# ADC.net
KiCad netlist of a schematic drawn in Altium Designer
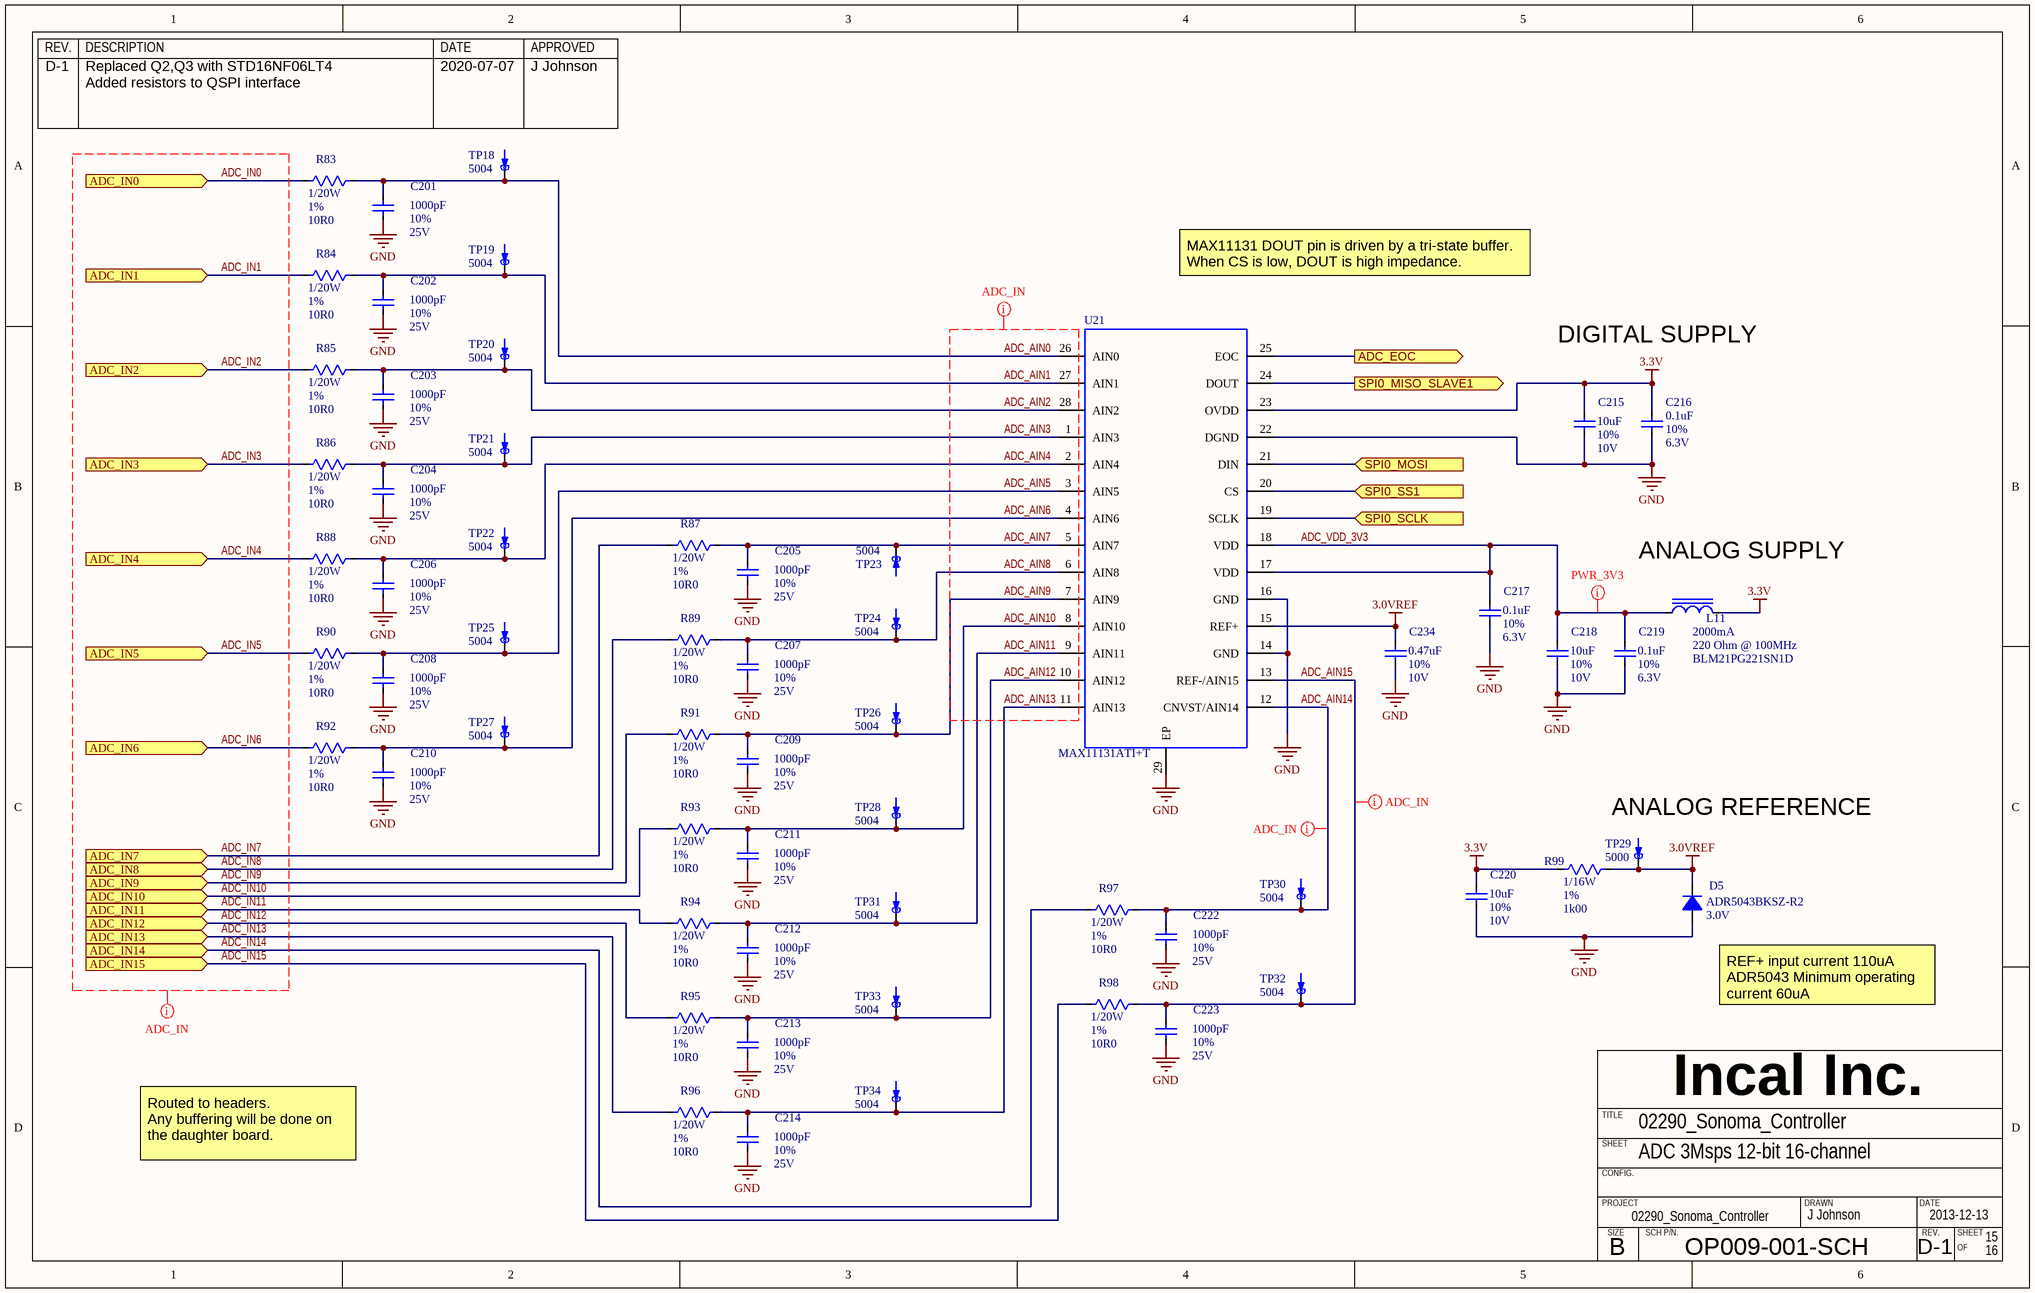
[diagram p0: ADC.SchDoc]

(export (version "E")
  (design (tool "Eeschema 10.0.6"))
  (components
    (comp (ref "C201")
      (value "1000pF")
      (footprint "CAPC0603X33N")
      (description "Capacitor ceramic, X5R, 1000pF, 25V, 10%, -55 to +85 C, EIA0201")
      (fields
        (field (name "TOLERANCE") "10%")
        (field (name "VOLTAGE") "25V")
        (field (name "Comment") "CAPACITOR_NP_TYPE1")
      )
      (libsource (lib "parts") (part "CAPACITOR_NP_TYPE1"))
    )
    (comp (ref "C202")
      (value "1000pF")
      (footprint "CAPC0603X33N")
      (description "Capacitor ceramic, X5R, 1000pF, 25V, 10%, -55 to +85 C, EIA0201")
      (fields
        (field (name "TOLERANCE") "10%")
        (field (name "VOLTAGE") "25V")
        (field (name "Comment") "CAPACITOR_NP_TYPE1")
      )
      (libsource (lib "parts") (part "CAPACITOR_NP_TYPE1"))
    )
    (comp (ref "C203")
      (value "1000pF")
      (footprint "CAPC0603X33N")
      (description "Capacitor ceramic, X5R, 1000pF, 25V, 10%, -55 to +85 C, EIA0201")
      (fields
        (field (name "TOLERANCE") "10%")
        (field (name "VOLTAGE") "25V")
        (field (name "Comment") "CAPACITOR_NP_TYPE1")
      )
      (libsource (lib "parts") (part "CAPACITOR_NP_TYPE1"))
    )
    (comp (ref "C204")
      (value "1000pF")
      (footprint "CAPC0603X33N")
      (description "Capacitor ceramic, X5R, 1000pF, 25V, 10%, -55 to +85 C, EIA0201")
      (fields
        (field (name "TOLERANCE") "10%")
        (field (name "VOLTAGE") "25V")
        (field (name "Comment") "CAPACITOR_NP_TYPE1")
      )
      (libsource (lib "parts") (part "CAPACITOR_NP_TYPE1"))
    )
    (comp (ref "C205")
      (value "1000pF")
      (footprint "CAPC0603X33N")
      (description "Capacitor ceramic, X5R, 1000pF, 25V, 10%, -55 to +85 C, EIA0201")
      (fields
        (field (name "TOLERANCE") "10%")
        (field (name "VOLTAGE") "25V")
        (field (name "Comment") "CAPACITOR_NP_TYPE1")
      )
      (libsource (lib "parts") (part "CAPACITOR_NP_TYPE1"))
    )
    (comp (ref "C206")
      (value "1000pF")
      (footprint "CAPC0603X33N")
      (description "Capacitor ceramic, X5R, 1000pF, 25V, 10%, -55 to +85 C, EIA0201")
      (fields
        (field (name "TOLERANCE") "10%")
        (field (name "VOLTAGE") "25V")
        (field (name "Comment") "CAPACITOR_NP_TYPE1")
      )
      (libsource (lib "parts") (part "CAPACITOR_NP_TYPE1"))
    )
    (comp (ref "C207")
      (value "1000pF")
      (footprint "CAPC0603X33N")
      (description "Capacitor ceramic, X5R, 1000pF, 25V, 10%, -55 to +85 C, EIA0201")
      (fields
        (field (name "TOLERANCE") "10%")
        (field (name "VOLTAGE") "25V")
        (field (name "Comment") "CAPACITOR_NP_TYPE1")
      )
      (libsource (lib "parts") (part "CAPACITOR_NP_TYPE1"))
    )
    (comp (ref "C208")
      (value "1000pF")
      (footprint "CAPC0603X33N")
      (description "Capacitor ceramic, X5R, 1000pF, 25V, 10%, -55 to +85 C, EIA0201")
      (fields
        (field (name "TOLERANCE") "10%")
        (field (name "VOLTAGE") "25V")
        (field (name "Comment") "CAPACITOR_NP_TYPE1")
      )
      (libsource (lib "parts") (part "CAPACITOR_NP_TYPE1"))
    )
    (comp (ref "C209")
      (value "1000pF")
      (footprint "CAPC0603X33N")
      (description "Capacitor ceramic, X5R, 1000pF, 25V, 10%, -55 to +85 C, EIA0201")
      (fields
        (field (name "TOLERANCE") "10%")
        (field (name "VOLTAGE") "25V")
        (field (name "Comment") "CAPACITOR_NP_TYPE1")
      )
      (libsource (lib "parts") (part "CAPACITOR_NP_TYPE1"))
    )
    (comp (ref "C210")
      (value "1000pF")
      (footprint "CAPC0603X33N")
      (description "Capacitor ceramic, X5R, 1000pF, 25V, 10%, -55 to +85 C, EIA0201")
      (fields
        (field (name "TOLERANCE") "10%")
        (field (name "VOLTAGE") "25V")
        (field (name "Comment") "CAPACITOR_NP_TYPE1")
      )
      (libsource (lib "parts") (part "CAPACITOR_NP_TYPE1"))
    )
    (comp (ref "C211")
      (value "1000pF")
      (footprint "CAPC0603X33N")
      (description "Capacitor ceramic, X5R, 1000pF, 25V, 10%, -55 to +85 C, EIA0201")
      (fields
        (field (name "TOLERANCE") "10%")
        (field (name "VOLTAGE") "25V")
        (field (name "Comment") "CAPACITOR_NP_TYPE1")
      )
      (libsource (lib "parts") (part "CAPACITOR_NP_TYPE1"))
    )
    (comp (ref "C212")
      (value "1000pF")
      (footprint "CAPC0603X33N")
      (description "Capacitor ceramic, X5R, 1000pF, 25V, 10%, -55 to +85 C, EIA0201")
      (fields
        (field (name "TOLERANCE") "10%")
        (field (name "VOLTAGE") "25V")
        (field (name "Comment") "CAPACITOR_NP_TYPE1")
      )
      (libsource (lib "parts") (part "CAPACITOR_NP_TYPE1"))
    )
    (comp (ref "C213")
      (value "1000pF")
      (footprint "CAPC0603X33N")
      (description "Capacitor ceramic, X5R, 1000pF, 25V, 10%, -55 to +85 C, EIA0201")
      (fields
        (field (name "TOLERANCE") "10%")
        (field (name "VOLTAGE") "25V")
        (field (name "Comment") "CAPACITOR_NP_TYPE1")
      )
      (libsource (lib "parts") (part "CAPACITOR_NP_TYPE1"))
    )
    (comp (ref "C214")
      (value "1000pF")
      (footprint "CAPC0603X33N")
      (description "Capacitor ceramic, X5R, 1000pF, 25V, 10%, -55 to +85 C, EIA0201")
      (fields
        (field (name "TOLERANCE") "10%")
        (field (name "VOLTAGE") "25V")
        (field (name "Comment") "CAPACITOR_NP_TYPE1")
      )
      (libsource (lib "parts") (part "CAPACITOR_NP_TYPE1"))
    )
    (comp (ref "C215")
      (value "10uF")
      (footprint "CAPC1608X38N")
      (description "Capacitor ceramic, X5R, 10uF, 10V, 10%, -55 to +85 C, EIA0603")
      (fields
        (field (name "TOLERANCE") "10%")
        (field (name "VOLTAGE") "10V")
        (field (name "Comment") "CAPACITOR_NP_TYPE1")
      )
      (libsource (lib "parts") (part "CAPACITOR_NP_TYPE1"))
    )
    (comp (ref "C216")
      (value "0.1uF")
      (footprint "CAPC0603X33N")
      (description "Capacitor ceramic, X5R, 0.1uF, 6.3V, 10%, -55 to +125 C, EIA0201")
      (fields
        (field (name "TOLERANCE") "10%")
        (field (name "VOLTAGE") "6.3V")
        (field (name "Comment") "CAPACITOR_NP_TYPE1")
      )
      (libsource (lib "parts") (part "CAPACITOR_NP_TYPE1"))
    )
    (comp (ref "C217")
      (value "0.1uF")
      (footprint "CAPC0603X33N")
      (description "Capacitor ceramic, X5R, 0.1uF, 6.3V, 10%, -55 to +125 C, EIA0201")
      (fields
        (field (name "TOLERANCE") "10%")
        (field (name "VOLTAGE") "6.3V")
        (field (name "Comment") "CAPACITOR_NP_TYPE1")
      )
      (libsource (lib "parts") (part "CAPACITOR_NP_TYPE1"))
    )
    (comp (ref "C218")
      (value "10uF")
      (footprint "CAPC1608X38N")
      (description "Capacitor ceramic, X5R, 10uF, 10V, 10%, -55 to +85 C, EIA0603")
      (fields
        (field (name "TOLERANCE") "10%")
        (field (name "VOLTAGE") "10V")
        (field (name "Comment") "CAPACITOR_NP_TYPE1")
      )
      (libsource (lib "parts") (part "CAPACITOR_NP_TYPE1"))
    )
    (comp (ref "C219")
      (value "0.1uF")
      (footprint "CAPC0603X33N")
      (description "Capacitor ceramic, X5R, 0.1uF, 6.3V, 10%, -55 to +125 C, EIA0201")
      (fields
        (field (name "TOLERANCE") "10%")
        (field (name "VOLTAGE") "6.3V")
        (field (name "Comment") "CAPACITOR_NP_TYPE1")
      )
      (libsource (lib "parts") (part "CAPACITOR_NP_TYPE1"))
    )
    (comp (ref "C220")
      (value "10uF")
      (footprint "CAPC1608X38N")
      (description "Capacitor ceramic, X5R, 10uF, 10V, 10%, -55 to +85 C, EIA0603")
      (fields
        (field (name "TOLERANCE") "10%")
        (field (name "VOLTAGE") "10V")
        (field (name "Comment") "CAPACITOR_NP_TYPE1")
      )
      (libsource (lib "parts") (part "CAPACITOR_NP_TYPE1"))
    )
    (comp (ref "C222")
      (value "1000pF")
      (footprint "CAPC0603X33N")
      (description "Capacitor ceramic, X5R, 1000pF, 25V, 10%, -55 to +85 C, EIA0201")
      (fields
        (field (name "TOLERANCE") "10%")
        (field (name "VOLTAGE") "25V")
        (field (name "Comment") "CAPACITOR_NP_TYPE1")
      )
      (libsource (lib "parts") (part "CAPACITOR_NP_TYPE1"))
    )
    (comp (ref "C223")
      (value "1000pF")
      (footprint "CAPC0603X33N")
      (description "Capacitor ceramic, X5R, 1000pF, 25V, 10%, -55 to +85 C, EIA0201")
      (fields
        (field (name "TOLERANCE") "10%")
        (field (name "VOLTAGE") "25V")
        (field (name "Comment") "CAPACITOR_NP_TYPE1")
      )
      (libsource (lib "parts") (part "CAPACITOR_NP_TYPE1"))
    )
    (comp (ref "C234")
      (value "0.47uF")
      (footprint "CAPC1005X55N")
      (description "Capacitor ceramic, X5R, 0.47uF, 10V, 10%, -55 to +85 C, EIA0402")
      (fields
        (field (name "TOLERANCE") "10%")
        (field (name "VOLTAGE") "10V")
        (field (name "Comment") "CAPACITOR_NP_TYPE1")
      )
      (libsource (lib "parts") (part "CAPACITOR_NP_TYPE1"))
    )
    (comp (ref "D5")
      (value "3.0V")
      (footprint "SOT65P210X110-3N")
      (description "Reference Shunt 3.0V, 3-lead SC70")
      (fields
        (field (name "TOLERANCE") "0.1%")
        (field (name "MFG PART NUMBER 1") "ADR5043BKSZ-R2")
        (field (name "Comment") "DIODE_TYPE3")
      )
      (libsource (lib "parts") (part "DIODE_TYPE3"))
    )
    (comp (ref "L11")
      (value "220 Ohm @ 100MHz")
      (footprint "INDC2012X85N")
      (description "Ferrite chip, 220 Ohm @ 100MHz, 2000mA, 25%, -55 to +125 C, 0805")
      (fields
        (field (name "TOLERANCE") "25%")
        (field (name "CURRENT") "2000mA")
        (field (name "MFG PART NUMBER 1") "BLM21PG221SN1D")
        (field (name "Comment") "INDUCTOR_CORE_TYPE1")
      )
      (libsource (lib "parts") (part "INDUCTOR_CORE_TYPE1"))
    )
    (comp (ref "R83")
      (value "10R0")
      (footprint "RESC1005X33N")
      (description "Resistor, 10R0, 1/20W, 1%, -50 to +155 C, EIA0201, EIA(M)0603")
      (fields (field (name "VOLTAGE") "50V") (field (name "POWER") "1/20W") (field (name "TOLERANCE") "1%"))
      (libsource (lib "parts") (part "RESISTOR_TYPE1"))
    )
    (comp (ref "R84")
      (value "10R0")
      (footprint "RESC1005X33N")
      (description "Resistor, 10R0, 1/20W, 1%, -50 to +155 C, EIA0201, EIA(M)0603")
      (fields (field (name "VOLTAGE") "50V") (field (name "POWER") "1/20W") (field (name "TOLERANCE") "1%"))
      (libsource (lib "parts") (part "RESISTOR_TYPE1"))
    )
    (comp (ref "R85")
      (value "10R0")
      (footprint "RESC1005X33N")
      (description "Resistor, 10R0, 1/20W, 1%, -50 to +155 C, EIA0201, EIA(M)0603")
      (fields (field (name "VOLTAGE") "50V") (field (name "POWER") "1/20W") (field (name "TOLERANCE") "1%"))
      (libsource (lib "parts") (part "RESISTOR_TYPE1"))
    )
    (comp (ref "R86")
      (value "10R0")
      (footprint "RESC1005X33N")
      (description "Resistor, 10R0, 1/20W, 1%, -50 to +155 C, EIA0201, EIA(M)0603")
      (fields (field (name "VOLTAGE") "50V") (field (name "POWER") "1/20W") (field (name "TOLERANCE") "1%"))
      (libsource (lib "parts") (part "RESISTOR_TYPE1"))
    )
    (comp (ref "R87")
      (value "10R0")
      (footprint "RESC1005X33N")
      (description "Resistor, 10R0, 1/20W, 1%, -50 to +155 C, EIA0201, EIA(M)0603")
      (fields (field (name "VOLTAGE") "50V") (field (name "POWER") "1/20W") (field (name "TOLERANCE") "1%"))
      (libsource (lib "parts") (part "RESISTOR_TYPE1"))
    )
    (comp (ref "R88")
      (value "10R0")
      (footprint "RESC1005X33N")
      (description "Resistor, 10R0, 1/20W, 1%, -50 to +155 C, EIA0201, EIA(M)0603")
      (fields (field (name "VOLTAGE") "50V") (field (name "POWER") "1/20W") (field (name "TOLERANCE") "1%"))
      (libsource (lib "parts") (part "RESISTOR_TYPE1"))
    )
    (comp (ref "R89")
      (value "10R0")
      (footprint "RESC1005X33N")
      (description "Resistor, 10R0, 1/20W, 1%, -50 to +155 C, EIA0201, EIA(M)0603")
      (fields (field (name "VOLTAGE") "50V") (field (name "POWER") "1/20W") (field (name "TOLERANCE") "1%"))
      (libsource (lib "parts") (part "RESISTOR_TYPE1"))
    )
    (comp (ref "R90")
      (value "10R0")
      (footprint "RESC1005X33N")
      (description "Resistor, 10R0, 1/20W, 1%, -50 to +155 C, EIA0201, EIA(M)0603")
      (fields (field (name "VOLTAGE") "50V") (field (name "POWER") "1/20W") (field (name "TOLERANCE") "1%"))
      (libsource (lib "parts") (part "RESISTOR_TYPE1"))
    )
    (comp (ref "R91")
      (value "10R0")
      (footprint "RESC1005X33N")
      (description "Resistor, 10R0, 1/20W, 1%, -50 to +155 C, EIA0201, EIA(M)0603")
      (fields (field (name "VOLTAGE") "50V") (field (name "POWER") "1/20W") (field (name "TOLERANCE") "1%"))
      (libsource (lib "parts") (part "RESISTOR_TYPE1"))
    )
    (comp (ref "R92")
      (value "10R0")
      (footprint "RESC1005X33N")
      (description "Resistor, 10R0, 1/20W, 1%, -50 to +155 C, EIA0201, EIA(M)0603")
      (fields (field (name "VOLTAGE") "50V") (field (name "POWER") "1/20W") (field (name "TOLERANCE") "1%"))
      (libsource (lib "parts") (part "RESISTOR_TYPE1"))
    )
    (comp (ref "R93")
      (value "10R0")
      (footprint "RESC1005X33N")
      (description "Resistor, 10R0, 1/20W, 1%, -50 to +155 C, EIA0201, EIA(M)0603")
      (fields (field (name "VOLTAGE") "50V") (field (name "POWER") "1/20W") (field (name "TOLERANCE") "1%"))
      (libsource (lib "parts") (part "RESISTOR_TYPE1"))
    )
    (comp (ref "R94")
      (value "10R0")
      (footprint "RESC1005X33N")
      (description "Resistor, 10R0, 1/20W, 1%, -50 to +155 C, EIA0201, EIA(M)0603")
      (fields (field (name "VOLTAGE") "50V") (field (name "POWER") "1/20W") (field (name "TOLERANCE") "1%"))
      (libsource (lib "parts") (part "RESISTOR_TYPE1"))
    )
    (comp (ref "R95")
      (value "10R0")
      (footprint "RESC1005X33N")
      (description "Resistor, 10R0, 1/20W, 1%, -50 to +155 C, EIA0201, EIA(M)0603")
      (fields (field (name "VOLTAGE") "50V") (field (name "POWER") "1/20W") (field (name "TOLERANCE") "1%"))
      (libsource (lib "parts") (part "RESISTOR_TYPE1"))
    )
    (comp (ref "R96")
      (value "10R0")
      (footprint "RESC1005X33N")
      (description "Resistor, 10R0, 1/20W, 1%, -50 to +155 C, EIA0201, EIA(M)0603")
      (fields (field (name "VOLTAGE") "50V") (field (name "POWER") "1/20W") (field (name "TOLERANCE") "1%"))
      (libsource (lib "parts") (part "RESISTOR_TYPE1"))
    )
    (comp (ref "R97")
      (value "10R0")
      (footprint "RESC1005X33N")
      (description "Resistor, 10R0, 1/20W, 1%, -50 to +155 C, EIA0201, EIA(M)0603")
      (fields (field (name "VOLTAGE") "50V") (field (name "POWER") "1/20W") (field (name "TOLERANCE") "1%"))
      (libsource (lib "parts") (part "RESISTOR_TYPE1"))
    )
    (comp (ref "R98")
      (value "10R0")
      (footprint "RESC1005X33N")
      (description "Resistor, 10R0, 1/20W, 1%, -50 to +155 C, EIA0201, EIA(M)0603")
      (fields (field (name "VOLTAGE") "50V") (field (name "POWER") "1/20W") (field (name "TOLERANCE") "1%"))
      (libsource (lib "parts") (part "RESISTOR_TYPE1"))
    )
    (comp (ref "R99")
      (value "1k00")
      (footprint "RESC1005X33N")
      (description "Resistor, 1k00, 1/16W, 1%, -55 to +155 C, EIA0402")
      (fields (field (name "VOLTAGE") "50V") (field (name "POWER") "1/16W") (field (name "TOLERANCE") "1%"))
      (libsource (lib "parts") (part "RESISTOR_TYPE1"))
    )
    (comp (ref "TP18")
      (value "5004")
      (footprint "KEY_5004")
      (description "Test point bead, yellow, Keystone Electronics, Thru-hole,")
      (fields (field (name "POWER") "Pow") (field (name "VOLTAGE") "Vol"))
      (libsource (lib "parts") (part "TEST_POINT_TYPE4"))
    )
    (comp (ref "TP19")
      (value "5004")
      (footprint "KEY_5004")
      (description "Test point bead, yellow, Keystone Electronics, Thru-hole,")
      (fields (field (name "POWER") "Pow") (field (name "VOLTAGE") "Vol"))
      (libsource (lib "parts") (part "TEST_POINT_TYPE4"))
    )
    (comp (ref "TP20")
      (value "5004")
      (footprint "KEY_5004")
      (description "Test point bead, yellow, Keystone Electronics, Thru-hole,")
      (fields (field (name "POWER") "Pow") (field (name "VOLTAGE") "Vol"))
      (libsource (lib "parts") (part "TEST_POINT_TYPE4"))
    )
    (comp (ref "TP21")
      (value "5004")
      (footprint "KEY_5004")
      (description "Test point bead, yellow, Keystone Electronics, Thru-hole,")
      (fields (field (name "POWER") "Pow") (field (name "VOLTAGE") "Vol"))
      (libsource (lib "parts") (part "TEST_POINT_TYPE4"))
    )
    (comp (ref "TP22")
      (value "5004")
      (footprint "KEY_5004")
      (description "Test point bead, yellow, Keystone Electronics, Thru-hole,")
      (fields (field (name "POWER") "Pow") (field (name "VOLTAGE") "Vol"))
      (libsource (lib "parts") (part "TEST_POINT_TYPE4"))
    )
    (comp (ref "TP23")
      (value "5004")
      (footprint "KEY_5004")
      (description "Test point bead, yellow, Keystone Electronics, Thru-hole,")
      (fields (field (name "POWER") "Pow") (field (name "VOLTAGE") "Vol"))
      (libsource (lib "") (part "TEST_POINT_TYPE4_1"))
    )
    (comp (ref "TP24")
      (value "5004")
      (footprint "KEY_5004")
      (description "Test point bead, yellow, Keystone Electronics, Thru-hole,")
      (fields (field (name "POWER") "Pow") (field (name "VOLTAGE") "Vol"))
      (libsource (lib "parts") (part "TEST_POINT_TYPE4"))
    )
    (comp (ref "TP25")
      (value "5004")
      (footprint "KEY_5004")
      (description "Test point bead, yellow, Keystone Electronics, Thru-hole,")
      (fields (field (name "POWER") "Pow") (field (name "VOLTAGE") "Vol"))
      (libsource (lib "parts") (part "TEST_POINT_TYPE4"))
    )
    (comp (ref "TP26")
      (value "5004")
      (footprint "KEY_5004")
      (description "Test point bead, yellow, Keystone Electronics, Thru-hole,")
      (fields (field (name "POWER") "Pow") (field (name "VOLTAGE") "Vol"))
      (libsource (lib "parts") (part "TEST_POINT_TYPE4"))
    )
    (comp (ref "TP27")
      (value "5004")
      (footprint "KEY_5004")
      (description "Test point bead, yellow, Keystone Electronics, Thru-hole,")
      (fields (field (name "POWER") "Pow") (field (name "VOLTAGE") "Vol"))
      (libsource (lib "parts") (part "TEST_POINT_TYPE4"))
    )
    (comp (ref "TP28")
      (value "5004")
      (footprint "KEY_5004")
      (description "Test point bead, yellow, Keystone Electronics, Thru-hole,")
      (fields (field (name "POWER") "Pow") (field (name "VOLTAGE") "Vol"))
      (libsource (lib "parts") (part "TEST_POINT_TYPE4"))
    )
    (comp (ref "TP29")
      (value "5000")
      (footprint "KEY_5000")
      (description "Test point bead, red, Keystone Electronics, Thru-hole,")
      (fields (field (name "POWER") "Pow") (field (name "VOLTAGE") "Vol"))
      (libsource (lib "parts") (part "TEST_POINT_TYPE4"))
    )
    (comp (ref "TP30")
      (value "5004")
      (footprint "KEY_5004")
      (description "Test point bead, yellow, Keystone Electronics, Thru-hole,")
      (fields (field (name "POWER") "Pow") (field (name "VOLTAGE") "Vol"))
      (libsource (lib "parts") (part "TEST_POINT_TYPE4"))
    )
    (comp (ref "TP31")
      (value "5004")
      (footprint "KEY_5004")
      (description "Test point bead, yellow, Keystone Electronics, Thru-hole,")
      (fields (field (name "POWER") "Pow") (field (name "VOLTAGE") "Vol"))
      (libsource (lib "parts") (part "TEST_POINT_TYPE4"))
    )
    (comp (ref "TP32")
      (value "5004")
      (footprint "KEY_5004")
      (description "Test point bead, yellow, Keystone Electronics, Thru-hole,")
      (fields (field (name "POWER") "Pow") (field (name "VOLTAGE") "Vol"))
      (libsource (lib "parts") (part "TEST_POINT_TYPE4"))
    )
    (comp (ref "TP33")
      (value "5004")
      (footprint "KEY_5004")
      (description "Test point bead, yellow, Keystone Electronics, Thru-hole,")
      (fields (field (name "POWER") "Pow") (field (name "VOLTAGE") "Vol"))
      (libsource (lib "parts") (part "TEST_POINT_TYPE4"))
    )
    (comp (ref "TP34")
      (value "5004")
      (footprint "KEY_5004")
      (description "Test point bead, yellow, Keystone Electronics, Thru-hole,")
      (fields (field (name "POWER") "Pow") (field (name "VOLTAGE") "Vol"))
      (libsource (lib "parts") (part "TEST_POINT_TYPE4"))
    )
    (comp (ref "U21")
      (value "MAX11131ATI+T")
      (footprint "TQFN50P500X500X75-28N")
      (description "ADC 12bit, 3Msps, 16 channels,2.35V to 3.6V, TQFN, -40 to +125 C")
      (libsource (lib "parts") (part "MAX11131ATI+T"))
    )
  )
  (nets
    (net (code "1") (name "/ADC_AIN0") (class "Default")
      (node (ref "C201") (pin "1") (pinfunction "1_1") (pintype "passive"))
      (node (ref "R83") (pin "2") (pinfunction "2_2") (pintype "passive"))
      (node (ref "TP18") (pin "1") (pinfunction "1_1") (pintype "passive"))
      (node (ref "U21") (pin "26") (pinfunction "AIN0_26") (pintype "passive"))
    )
    (net (code "2") (name "/ADC_AIN1") (class "Default")
      (node (ref "C202") (pin "1") (pinfunction "1_1") (pintype "passive"))
      (node (ref "R84") (pin "2") (pinfunction "2_2") (pintype "passive"))
      (node (ref "TP19") (pin "1") (pinfunction "1_1") (pintype "passive"))
      (node (ref "U21") (pin "27") (pinfunction "AIN1_27") (pintype "passive"))
    )
    (net (code "3") (name "/ADC_AIN2") (class "Default")
      (node (ref "C203") (pin "1") (pinfunction "1_1") (pintype "passive"))
      (node (ref "R85") (pin "2") (pinfunction "2_2") (pintype "passive"))
      (node (ref "TP20") (pin "1") (pinfunction "1_1") (pintype "passive"))
      (node (ref "U21") (pin "28") (pinfunction "AIN2_28") (pintype "passive"))
    )
    (net (code "4") (name "/ADC_AIN3") (class "Default")
      (node (ref "C204") (pin "1") (pinfunction "1_1") (pintype "passive"))
      (node (ref "R86") (pin "2") (pinfunction "2_2") (pintype "passive"))
      (node (ref "TP21") (pin "1") (pinfunction "1_1") (pintype "passive"))
      (node (ref "U21") (pin "1") (pinfunction "AIN3_1") (pintype "passive"))
    )
    (net (code "5") (name "/ADC_AIN4") (class "Default")
      (node (ref "C206") (pin "1") (pinfunction "1_1") (pintype "passive"))
      (node (ref "R88") (pin "2") (pinfunction "2_2") (pintype "passive"))
      (node (ref "TP22") (pin "1") (pinfunction "1_1") (pintype "passive"))
      (node (ref "U21") (pin "2") (pinfunction "AIN4_2") (pintype "passive"))
    )
    (net (code "6") (name "/ADC_AIN5") (class "Default")
      (node (ref "C208") (pin "1") (pinfunction "1_1") (pintype "passive"))
      (node (ref "R90") (pin "2") (pinfunction "2_2") (pintype "passive"))
      (node (ref "TP25") (pin "1") (pinfunction "1_1") (pintype "passive"))
      (node (ref "U21") (pin "3") (pinfunction "AIN5_3") (pintype "passive"))
    )
    (net (code "7") (name "/ADC_AIN6") (class "Default")
      (node (ref "C210") (pin "1") (pinfunction "1_1") (pintype "passive"))
      (node (ref "R92") (pin "2") (pinfunction "2_2") (pintype "passive"))
      (node (ref "TP27") (pin "1") (pinfunction "1_1") (pintype "passive"))
      (node (ref "U21") (pin "4") (pinfunction "AIN6_4") (pintype "passive"))
    )
    (net (code "8") (name "/ADC_AIN7") (class "Default")
      (node (ref "C205") (pin "1") (pinfunction "1_1") (pintype "passive"))
      (node (ref "R87") (pin "2") (pinfunction "2_2") (pintype "passive"))
      (node (ref "TP23") (pin "1") (pinfunction "1_1") (pintype "passive"))
      (node (ref "U21") (pin "5") (pinfunction "AIN7_5") (pintype "passive"))
    )
    (net (code "9") (name "/ADC_AIN8") (class "Default")
      (node (ref "C207") (pin "1") (pinfunction "1_1") (pintype "passive"))
      (node (ref "R89") (pin "2") (pinfunction "2_2") (pintype "passive"))
      (node (ref "TP24") (pin "1") (pinfunction "1_1") (pintype "passive"))
      (node (ref "U21") (pin "6") (pinfunction "AIN8_6") (pintype "passive"))
    )
    (net (code "10") (name "/ADC_AIN9") (class "Default")
      (node (ref "C209") (pin "1") (pinfunction "1_1") (pintype "passive"))
      (node (ref "R91") (pin "2") (pinfunction "2_2") (pintype "passive"))
      (node (ref "TP26") (pin "1") (pinfunction "1_1") (pintype "passive"))
      (node (ref "U21") (pin "7") (pinfunction "AIN9_7") (pintype "passive"))
    )
    (net (code "11") (name "/ADC_AIN10") (class "Default")
      (node (ref "C211") (pin "1") (pinfunction "1_1") (pintype "passive"))
      (node (ref "R93") (pin "2") (pinfunction "2_2") (pintype "passive"))
      (node (ref "TP28") (pin "1") (pinfunction "1_1") (pintype "passive"))
      (node (ref "U21") (pin "8") (pinfunction "AIN10_8") (pintype "passive"))
    )
    (net (code "12") (name "/ADC_AIN11") (class "Default")
      (node (ref "C212") (pin "1") (pinfunction "1_1") (pintype "passive"))
      (node (ref "R94") (pin "2") (pinfunction "2_2") (pintype "passive"))
      (node (ref "TP31") (pin "1") (pinfunction "1_1") (pintype "passive"))
      (node (ref "U21") (pin "9") (pinfunction "AIN11_9") (pintype "passive"))
    )
    (net (code "13") (name "/ADC_AIN12") (class "Default")
      (node (ref "C213") (pin "1") (pinfunction "1_1") (pintype "passive"))
      (node (ref "R95") (pin "2") (pinfunction "2_2") (pintype "passive"))
      (node (ref "TP33") (pin "1") (pinfunction "1_1") (pintype "passive"))
      (node (ref "U21") (pin "10") (pinfunction "AIN12_10") (pintype "passive"))
    )
    (net (code "14") (name "/ADC_AIN13") (class "Default")
      (node (ref "C214") (pin "1") (pinfunction "1_1") (pintype "passive"))
      (node (ref "R96") (pin "2") (pinfunction "2_2") (pintype "passive"))
      (node (ref "TP34") (pin "1") (pinfunction "1_1") (pintype "passive"))
      (node (ref "U21") (pin "11") (pinfunction "AIN13_11") (pintype "passive"))
    )
    (net (code "15") (name "/ADC_AIN14") (class "Default")
      (node (ref "C222") (pin "1") (pinfunction "1_1") (pintype "passive"))
      (node (ref "R97") (pin "2") (pinfunction "2_2") (pintype "passive"))
      (node (ref "TP30") (pin "1") (pinfunction "1_1") (pintype "passive"))
      (node (ref "U21") (pin "12") (pinfunction "CNVST/AIN14_12") (pintype "passive"))
    )
    (net (code "16") (name "/ADC_AIN15") (class "Default")
      (node (ref "C223") (pin "1") (pinfunction "1_1") (pintype "passive"))
      (node (ref "R98") (pin "2") (pinfunction "2_2") (pintype "passive"))
      (node (ref "TP32") (pin "1") (pinfunction "1_1") (pintype "passive"))
      (node (ref "U21") (pin "13") (pinfunction "REF-/AIN15_13") (pintype "passive"))
    )
    (net (code "17") (name "/ADC_EOC") (class "Default")
      (node (ref "U21") (pin "25") (pinfunction "EOC_25") (pintype "passive"))
    )
    (net (code "18") (name "/ADC_IN0") (class "Default")
      (node (ref "R83") (pin "1") (pinfunction "1_1") (pintype "passive"))
    )
    (net (code "19") (name "/ADC_IN1") (class "Default")
      (node (ref "R84") (pin "1") (pinfunction "1_1") (pintype "passive"))
    )
    (net (code "20") (name "/ADC_IN2") (class "Default")
      (node (ref "R85") (pin "1") (pinfunction "1_1") (pintype "passive"))
    )
    (net (code "21") (name "/ADC_IN3") (class "Default")
      (node (ref "R86") (pin "1") (pinfunction "1_1") (pintype "passive"))
    )
    (net (code "22") (name "/ADC_IN4") (class "Default")
      (node (ref "R88") (pin "1") (pinfunction "1_1") (pintype "passive"))
    )
    (net (code "23") (name "/ADC_IN5") (class "Default")
      (node (ref "R90") (pin "1") (pinfunction "1_1") (pintype "passive"))
    )
    (net (code "24") (name "/ADC_IN6") (class "Default")
      (node (ref "R92") (pin "1") (pinfunction "1_1") (pintype "passive"))
    )
    (net (code "25") (name "/ADC_IN7") (class "Default")
      (node (ref "R87") (pin "1") (pinfunction "1_1") (pintype "passive"))
    )
    (net (code "26") (name "/ADC_IN8") (class "Default")
      (node (ref "R89") (pin "1") (pinfunction "1_1") (pintype "passive"))
    )
    (net (code "27") (name "/ADC_IN9") (class "Default")
      (node (ref "R91") (pin "1") (pinfunction "1_1") (pintype "passive"))
    )
    (net (code "28") (name "/ADC_IN10") (class "Default")
      (node (ref "R93") (pin "1") (pinfunction "1_1") (pintype "passive"))
    )
    (net (code "29") (name "/ADC_IN11") (class "Default")
      (node (ref "R94") (pin "1") (pinfunction "1_1") (pintype "passive"))
    )
    (net (code "30") (name "/ADC_IN12") (class "Default")
      (node (ref "R95") (pin "1") (pinfunction "1_1") (pintype "passive"))
    )
    (net (code "31") (name "/ADC_IN13") (class "Default")
      (node (ref "R96") (pin "1") (pinfunction "1_1") (pintype "passive"))
    )
    (net (code "32") (name "/ADC_IN14") (class "Default")
      (node (ref "R97") (pin "1") (pinfunction "1_1") (pintype "passive"))
    )
    (net (code "33") (name "/ADC_IN15") (class "Default")
      (node (ref "R98") (pin "1") (pinfunction "1_1") (pintype "passive"))
    )
    (net (code "34") (name "/ADC_VDD_3V3") (class "Default")
      (node (ref "C217") (pin "1") (pinfunction "1_1") (pintype "passive"))
      (node (ref "C218") (pin "1") (pinfunction "1_1") (pintype "passive"))
      (node (ref "C219") (pin "1") (pinfunction "1_1") (pintype "passive"))
      (node (ref "L11") (pin "1") (pinfunction "1_1") (pintype "passive"))
      (node (ref "U21") (pin "17") (pinfunction "VDD_17") (pintype "passive"))
      (node (ref "U21") (pin "18") (pinfunction "VDD_18") (pintype "passive"))
    )
    (net (code "35") (name "/SPI0_MISO_SLAVE1") (class "Default")
      (node (ref "U21") (pin "24") (pinfunction "DOUT_24") (pintype "passive"))
    )
    (net (code "36") (name "/SPI0_MOSI") (class "Default")
      (node (ref "U21") (pin "21") (pinfunction "DIN_21") (pintype "passive"))
    )
    (net (code "37") (name "/SPI0_SCLK") (class "Default")
      (node (ref "U21") (pin "19") (pinfunction "SCLK_19") (pintype "passive"))
    )
    (net (code "38") (name "/SPI0_SS1") (class "Default")
      (node (ref "U21") (pin "20") (pinfunction "CS_20") (pintype "passive"))
    )
    (net (code "39") (name "3.0VREF") (class "Default")
      (node (ref "C234") (pin "1") (pinfunction "1_1") (pintype "passive"))
      (node (ref "D5") (pin "1") (pinfunction "K_1") (pintype "passive"))
      (node (ref "R99") (pin "2") (pinfunction "2_2") (pintype "passive"))
      (node (ref "TP29") (pin "1") (pinfunction "1_1") (pintype "passive"))
      (node (ref "U21") (pin "15") (pinfunction "REF+_15") (pintype "passive"))
    )
    (net (code "40") (name "3.3V") (class "Default")
      (node (ref "C215") (pin "1") (pinfunction "1_1") (pintype "passive"))
      (node (ref "C216") (pin "1") (pinfunction "1_1") (pintype "passive"))
      (node (ref "C220") (pin "1") (pinfunction "1_1") (pintype "passive"))
      (node (ref "L11") (pin "2") (pinfunction "2_2") (pintype "passive"))
      (node (ref "R99") (pin "1") (pinfunction "1_1") (pintype "passive"))
      (node (ref "U21") (pin "23") (pinfunction "OVDD_23") (pintype "passive"))
    )
    (net (code "41") (name "GND") (class "Default")
      (node (ref "C201") (pin "2") (pinfunction "2_2") (pintype "passive"))
      (node (ref "C202") (pin "2") (pinfunction "2_2") (pintype "passive"))
      (node (ref "C203") (pin "2") (pinfunction "2_2") (pintype "passive"))
      (node (ref "C204") (pin "2") (pinfunction "2_2") (pintype "passive"))
      (node (ref "C205") (pin "2") (pinfunction "2_2") (pintype "passive"))
      (node (ref "C206") (pin "2") (pinfunction "2_2") (pintype "passive"))
      (node (ref "C207") (pin "2") (pinfunction "2_2") (pintype "passive"))
      (node (ref "C208") (pin "2") (pinfunction "2_2") (pintype "passive"))
      (node (ref "C209") (pin "2") (pinfunction "2_2") (pintype "passive"))
      (node (ref "C210") (pin "2") (pinfunction "2_2") (pintype "passive"))
      (node (ref "C211") (pin "2") (pinfunction "2_2") (pintype "passive"))
      (node (ref "C212") (pin "2") (pinfunction "2_2") (pintype "passive"))
      (node (ref "C213") (pin "2") (pinfunction "2_2") (pintype "passive"))
      (node (ref "C214") (pin "2") (pinfunction "2_2") (pintype "passive"))
      (node (ref "C215") (pin "2") (pinfunction "2_2") (pintype "passive"))
      (node (ref "C216") (pin "2") (pinfunction "2_2") (pintype "passive"))
      (node (ref "C217") (pin "2") (pinfunction "2_2") (pintype "passive"))
      (node (ref "C218") (pin "2") (pinfunction "2_2") (pintype "passive"))
      (node (ref "C219") (pin "2") (pinfunction "2_2") (pintype "passive"))
      (node (ref "C220") (pin "2") (pinfunction "2_2") (pintype "passive"))
      (node (ref "C222") (pin "2") (pinfunction "2_2") (pintype "passive"))
      (node (ref "C223") (pin "2") (pinfunction "2_2") (pintype "passive"))
      (node (ref "C234") (pin "2") (pinfunction "2_2") (pintype "passive"))
      (node (ref "D5") (pin "2") (pinfunction "A_2") (pintype "passive"))
      (node (ref "U21") (pin "14") (pinfunction "GND_14") (pintype "passive"))
      (node (ref "U21") (pin "16") (pinfunction "GND_16") (pintype "passive"))
      (node (ref "U21") (pin "22") (pinfunction "DGND_22") (pintype "passive"))
      (node (ref "U21") (pin "29") (pinfunction "EP_29") (pintype "passive"))
    )
  )
)
